# Mechanical.net
KiCad netlist of a schematic drawn in Altium Designer
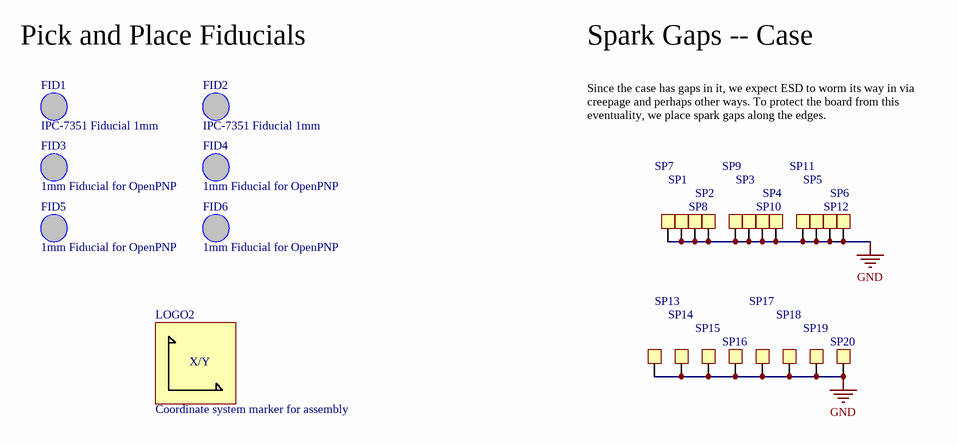
[diagram p0: Mechanical.SchDoc]

(export (version "E")
  (design (tool "Eeschema 10.0.6"))
  (components
    (comp (ref "FID1")
      (value "IPC-7351 Fiducial 1mm")
      (footprint "FIDUCIAL_1.5")
      (libsource (lib "Mechanical") (part "FIDUCIAL_1.5"))
    )
    (comp (ref "FID2")
      (value "IPC-7351 Fiducial 1mm")
      (footprint "FIDUCIAL_1.5")
      (libsource (lib "Mechanical") (part "FIDUCIAL_1.5"))
    )
    (comp (ref "FID3")
      (value "1mm Fiducial for OpenPNP")
      (footprint "FIDUCIAL-NEW")
      (libsource (lib "Mechanical") (part "FIDUCIAL_NEW"))
    )
    (comp (ref "FID4")
      (value "1mm Fiducial for OpenPNP")
      (footprint "FIDUCIAL-NEW")
      (libsource (lib "Mechanical") (part "FIDUCIAL_NEW"))
    )
    (comp (ref "FID5")
      (value "1mm Fiducial for OpenPNP")
      (footprint "FIDUCIAL-NEW")
      (libsource (lib "Mechanical") (part "FIDUCIAL_NEW"))
    )
    (comp (ref "FID6")
      (value "1mm Fiducial for OpenPNP")
      (footprint "FIDUCIAL-NEW")
      (libsource (lib "Mechanical") (part "FIDUCIAL_NEW"))
    )
    (comp (ref "LOGO2")
      (value "Coordinate system marker for assembly")
      (footprint "Coordinate System")
      (libsource (lib "Graphics") (part "CoordinateSystem"))
    )
    (comp (ref "SP1")
      (value "Spark Gap")
      (footprint "SparkGap")
      (description "Open square pad for spark gapping")
      (libsource (lib "PCBFeatures") (part "Spark Gap"))
    )
    (comp (ref "SP2")
      (value "Spark Gap")
      (footprint "SparkGap")
      (description "Open square pad for spark gapping")
      (libsource (lib "PCBFeatures") (part "Spark Gap"))
    )
    (comp (ref "SP3")
      (value "Spark Gap")
      (footprint "SparkGap")
      (description "Open square pad for spark gapping")
      (libsource (lib "PCBFeatures") (part "Spark Gap"))
    )
    (comp (ref "SP4")
      (value "Spark Gap")
      (footprint "SparkGap")
      (description "Open square pad for spark gapping")
      (libsource (lib "PCBFeatures") (part "Spark Gap"))
    )
    (comp (ref "SP5")
      (value "Spark Gap")
      (footprint "SparkGap")
      (description "Open square pad for spark gapping")
      (libsource (lib "PCBFeatures") (part "Spark Gap"))
    )
    (comp (ref "SP6")
      (value "Spark Gap")
      (footprint "SparkGap")
      (description "Open square pad for spark gapping")
      (libsource (lib "PCBFeatures") (part "Spark Gap"))
    )
    (comp (ref "SP7")
      (value "Spark Gap")
      (footprint "SparkGap")
      (description "Open square pad for spark gapping")
      (libsource (lib "PCBFeatures") (part "Spark Gap"))
    )
    (comp (ref "SP8")
      (value "Spark Gap")
      (footprint "SparkGap")
      (description "Open square pad for spark gapping")
      (libsource (lib "PCBFeatures") (part "Spark Gap"))
    )
    (comp (ref "SP9")
      (value "Spark Gap")
      (footprint "SparkGap")
      (description "Open square pad for spark gapping")
      (libsource (lib "PCBFeatures") (part "Spark Gap"))
    )
    (comp (ref "SP10")
      (value "Spark Gap")
      (footprint "SparkGap")
      (description "Open square pad for spark gapping")
      (libsource (lib "PCBFeatures") (part "Spark Gap"))
    )
    (comp (ref "SP11")
      (value "Spark Gap")
      (footprint "SparkGap")
      (description "Open square pad for spark gapping")
      (libsource (lib "PCBFeatures") (part "Spark Gap"))
    )
    (comp (ref "SP12")
      (value "Spark Gap")
      (footprint "SparkGap")
      (description "Open square pad for spark gapping")
      (libsource (lib "PCBFeatures") (part "Spark Gap"))
    )
    (comp (ref "SP13")
      (value "Spark Gap")
      (footprint "SparkGap")
      (description "Open square pad for spark gapping")
      (libsource (lib "PCBFeatures") (part "Spark Gap"))
    )
    (comp (ref "SP14")
      (value "Spark Gap")
      (footprint "SparkGap")
      (description "Open square pad for spark gapping")
      (libsource (lib "PCBFeatures") (part "Spark Gap"))
    )
    (comp (ref "SP15")
      (value "Spark Gap")
      (footprint "SparkGap")
      (description "Open square pad for spark gapping")
      (libsource (lib "PCBFeatures") (part "Spark Gap"))
    )
    (comp (ref "SP16")
      (value "Spark Gap")
      (footprint "SparkGap")
      (description "Open square pad for spark gapping")
      (libsource (lib "PCBFeatures") (part "Spark Gap"))
    )
    (comp (ref "SP17")
      (value "Spark Gap")
      (footprint "SparkGap")
      (description "Open square pad for spark gapping")
      (libsource (lib "PCBFeatures") (part "Spark Gap"))
    )
    (comp (ref "SP18")
      (value "Spark Gap")
      (footprint "SparkGap")
      (description "Open square pad for spark gapping")
      (libsource (lib "PCBFeatures") (part "Spark Gap"))
    )
    (comp (ref "SP19")
      (value "Spark Gap")
      (footprint "SparkGap")
      (description "Open square pad for spark gapping")
      (libsource (lib "PCBFeatures") (part "Spark Gap"))
    )
    (comp (ref "SP20")
      (value "Spark Gap")
      (footprint "SparkGap")
      (description "Open square pad for spark gapping")
      (libsource (lib "PCBFeatures") (part "Spark Gap"))
    )
  )
  (nets
    (net (code "1") (name "GND") (class "Default")
      (node (ref "SP1") (pin "1") (pinfunction "1_1") (pintype "passive"))
      (node (ref "SP10") (pin "1") (pinfunction "1_1") (pintype "passive"))
      (node (ref "SP11") (pin "1") (pinfunction "1_1") (pintype "passive"))
      (node (ref "SP12") (pin "1") (pinfunction "1_1") (pintype "passive"))
      (node (ref "SP13") (pin "1") (pinfunction "1_1") (pintype "passive"))
      (node (ref "SP14") (pin "1") (pinfunction "1_1") (pintype "passive"))
      (node (ref "SP15") (pin "1") (pinfunction "1_1") (pintype "passive"))
      (node (ref "SP16") (pin "1") (pinfunction "1_1") (pintype "passive"))
      (node (ref "SP17") (pin "1") (pinfunction "1_1") (pintype "passive"))
      (node (ref "SP18") (pin "1") (pinfunction "1_1") (pintype "passive"))
      (node (ref "SP19") (pin "1") (pinfunction "1_1") (pintype "passive"))
      (node (ref "SP2") (pin "1") (pinfunction "1_1") (pintype "passive"))
      (node (ref "SP20") (pin "1") (pinfunction "1_1") (pintype "passive"))
      (node (ref "SP3") (pin "1") (pinfunction "1_1") (pintype "passive"))
      (node (ref "SP4") (pin "1") (pinfunction "1_1") (pintype "passive"))
      (node (ref "SP5") (pin "1") (pinfunction "1_1") (pintype "passive"))
      (node (ref "SP6") (pin "1") (pinfunction "1_1") (pintype "passive"))
      (node (ref "SP7") (pin "1") (pinfunction "1_1") (pintype "passive"))
      (node (ref "SP8") (pin "1") (pinfunction "1_1") (pintype "passive"))
      (node (ref "SP9") (pin "1") (pinfunction "1_1") (pintype "passive"))
    )
    (net (code "2") (name "unconnected-(FID1-Pad1)") (class "Default")
      (node (ref "FID1") (pin "1") (pinfunction "1_1") (pintype "passive"))
    )
    (net (code "3") (name "unconnected-(FID2-Pad1)") (class "Default")
      (node (ref "FID2") (pin "1") (pinfunction "1_1") (pintype "passive"))
    )
    (net (code "4") (name "unconnected-(FID3-Pad1)") (class "Default")
      (node (ref "FID3") (pin "1") (pinfunction "1_1") (pintype "passive"))
    )
    (net (code "5") (name "unconnected-(FID4-Pad1)") (class "Default")
      (node (ref "FID4") (pin "1") (pinfunction "1_1") (pintype "passive"))
    )
    (net (code "6") (name "unconnected-(FID5-Pad1)") (class "Default")
      (node (ref "FID5") (pin "1") (pinfunction "1_1") (pintype "passive"))
    )
    (net (code "7") (name "unconnected-(FID6-Pad1)") (class "Default")
      (node (ref "FID6") (pin "1") (pinfunction "1_1") (pintype "passive"))
    )
  )
)
